# IR.net
KiCad netlist of a schematic drawn in Altium Designer
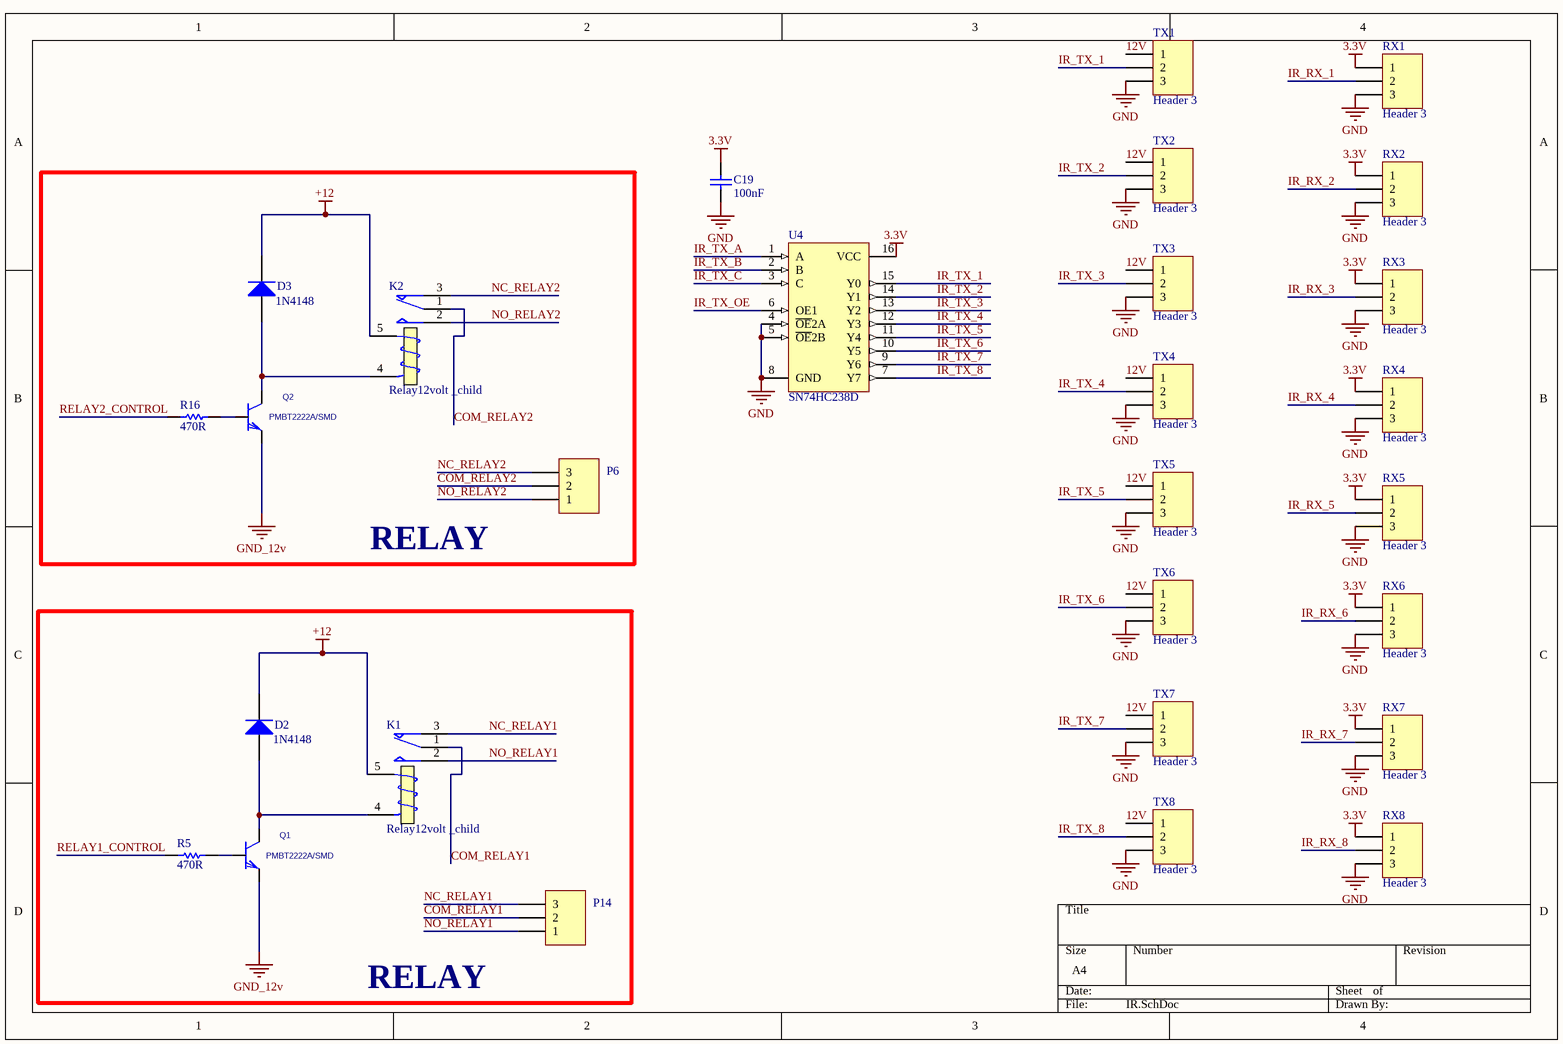
[diagram p0: IR.SchDoc]

(export (version "E")
  (design (tool "Eeschema 10.0.6"))
  (components
    (comp (ref "C19")
      (value "100nF")
      (footprint "0805")
      (description "Capacitor")
      (fields (field (name "PUBLISHER") "Altium Limited"))
      (libsource (lib "Miscellaneous Devices") (part "Cap"))
    )
    (comp (ref "D2")
      (value "1N4148")
      (footprint "diode smd")
      (description "1 Amp General Purpose Rectifier")
      (fields (field (name "PUBLISHER") "Altium Limited"))
      (libsource (lib "Miscellaneous Devices") (part "Diode 1N4007"))
    )
    (comp (ref "D3")
      (value "1N4148")
      (footprint "diode smd")
      (description "1 Amp General Purpose Rectifier")
      (fields (field (name "PUBLISHER") "Altium Limited"))
      (libsource (lib "Miscellaneous Devices") (part "Diode 1N4007"))
    )
    (comp (ref "K1")
      (value "Relay12volt _child")
      (footprint "relay")
      (description "SPDT Relay")
      (fields (field (name "PUBLISHER") "Altium Limited"))
      (libsource (lib "FLIB") (part "Relay"))
    )
    (comp (ref "K2")
      (value "Relay12volt _child")
      (footprint "relay")
      (description "SPDT Relay")
      (fields (field (name "PUBLISHER") "Altium Limited"))
      (libsource (lib "FLIB") (part "Relay"))
    )
    (comp (ref "P6")
      (value "kf301/3pin")
      (footprint "Blue Connector 1*3 -kf301")
      (fields (field (name "PUBLISHER") "Altium Limited"))
      (libsource (lib "") (part "Header 3_1"))
    )
    (comp (ref "P14")
      (value "kf301/3pin")
      (footprint "Blue Connector 1*3 -kf301")
      (fields (field (name "PUBLISHER") "Altium Limited"))
      (libsource (lib "") (part "Header 3_1"))
    )
    (comp (ref "Q1")
      (value "PMBT2222A/SMD")
      (footprint "transistoor1")
      (libsource (lib "*") (part "2N2222A/ZTX"))
    )
    (comp (ref "Q2")
      (value "PMBT2222A/SMD")
      (footprint "transistoor1")
      (libsource (lib "*") (part "2N2222A/ZTX"))
    )
    (comp (ref "R5")
      (value "470R")
      (footprint "res")
      (description "Resistor")
      (fields (field (name "PUBLISHER") "Altium Limited"))
      (libsource (lib "Miscellaneous Devices") (part "Res1"))
    )
    (comp (ref "R16")
      (value "470R")
      (footprint "res")
      (description "Resistor")
      (fields (field (name "PUBLISHER") "Altium Limited"))
      (libsource (lib "Miscellaneous Devices") (part "Res1"))
    )
    (comp (ref "RX1")
      (value "Header 3")
      (footprint "HDR1X3")
      (description "Header, 3-Pin")
      (fields (field (name "PUBLISHER") "Altium Limited"))
      (libsource (lib "Miscellaneous Connectors") (part "Header 3"))
    )
    (comp (ref "RX2")
      (value "Header 3")
      (footprint "HDR1X3")
      (description "Header, 3-Pin")
      (fields (field (name "PUBLISHER") "Altium Limited"))
      (libsource (lib "Miscellaneous Connectors") (part "Header 3"))
    )
    (comp (ref "RX3")
      (value "Header 3")
      (footprint "HDR1X3")
      (description "Header, 3-Pin")
      (fields (field (name "PUBLISHER") "Altium Limited"))
      (libsource (lib "Miscellaneous Connectors") (part "Header 3"))
    )
    (comp (ref "RX4")
      (value "Header 3")
      (footprint "HDR1X3")
      (description "Header, 3-Pin")
      (fields (field (name "PUBLISHER") "Altium Limited"))
      (libsource (lib "Miscellaneous Connectors") (part "Header 3"))
    )
    (comp (ref "RX5")
      (value "Header 3")
      (footprint "HDR1X3")
      (description "Header, 3-Pin")
      (fields (field (name "PUBLISHER") "Altium Limited"))
      (libsource (lib "Miscellaneous Connectors") (part "Header 3"))
    )
    (comp (ref "RX6")
      (value "Header 3")
      (footprint "HDR1X3")
      (description "Header, 3-Pin")
      (fields (field (name "PUBLISHER") "Altium Limited"))
      (libsource (lib "Miscellaneous Connectors") (part "Header 3"))
    )
    (comp (ref "RX7")
      (value "Header 3")
      (footprint "HDR1X3")
      (description "Header, 3-Pin")
      (fields (field (name "PUBLISHER") "Altium Limited"))
      (libsource (lib "Miscellaneous Connectors") (part "Header 3"))
    )
    (comp (ref "RX8")
      (value "Header 3")
      (footprint "HDR1X3")
      (description "Header, 3-Pin")
      (fields (field (name "PUBLISHER") "Altium Limited"))
      (libsource (lib "Miscellaneous Connectors") (part "Header 3"))
    )
    (comp (ref "TX1")
      (value "Header 3")
      (footprint "HDR1X3")
      (description "Header, 3-Pin")
      (fields (field (name "PUBLISHER") "Altium Limited"))
      (libsource (lib "Miscellaneous Connectors") (part "Header 3"))
    )
    (comp (ref "TX2")
      (value "Header 3")
      (footprint "HDR1X3")
      (description "Header, 3-Pin")
      (fields (field (name "PUBLISHER") "Altium Limited"))
      (libsource (lib "Miscellaneous Connectors") (part "Header 3"))
    )
    (comp (ref "TX3")
      (value "Header 3")
      (footprint "HDR1X3")
      (description "Header, 3-Pin")
      (fields (field (name "PUBLISHER") "Altium Limited"))
      (libsource (lib "Miscellaneous Connectors") (part "Header 3"))
    )
    (comp (ref "TX4")
      (value "Header 3")
      (footprint "HDR1X3")
      (description "Header, 3-Pin")
      (fields (field (name "PUBLISHER") "Altium Limited"))
      (libsource (lib "Miscellaneous Connectors") (part "Header 3"))
    )
    (comp (ref "TX5")
      (value "Header 3")
      (footprint "HDR1X3")
      (description "Header, 3-Pin")
      (fields (field (name "PUBLISHER") "Altium Limited"))
      (libsource (lib "Miscellaneous Connectors") (part "Header 3"))
    )
    (comp (ref "TX6")
      (value "Header 3")
      (footprint "HDR1X3")
      (description "Header, 3-Pin")
      (fields (field (name "PUBLISHER") "Altium Limited"))
      (libsource (lib "Miscellaneous Connectors") (part "Header 3"))
    )
    (comp (ref "TX7")
      (value "Header 3")
      (footprint "HDR1X3")
      (description "Header, 3-Pin")
      (fields (field (name "PUBLISHER") "Altium Limited"))
      (libsource (lib "Miscellaneous Connectors") (part "Header 3"))
    )
    (comp (ref "TX8")
      (value "Header 3")
      (footprint "HDR1X3")
      (description "Header, 3-Pin")
      (fields (field (name "PUBLISHER") "Altium Limited"))
      (libsource (lib "Miscellaneous Connectors") (part "Header 3"))
    )
    (comp (ref "U4")
      (value "SN74HC238D")
      (footprint "D016_N")
      (description "3-Line to 8-Line Decoder / Demultiplexer")
      (fields (field (name "PUBLISHER") "Altium Limited"))
      (libsource (lib "TI Logic Decoder Demux") (part "SN74HC238D"))
    )
  )
  (nets
    (net (code "1") (name "+12") (class "Default")
      (node (ref "D2") (pin "2") (pinfunction "K_2") (pintype "passive"))
      (node (ref "D3") (pin "2") (pinfunction "K_2") (pintype "passive"))
      (node (ref "K1") (pin "5") (pinfunction "5_5") (pintype "passive"))
      (node (ref "K2") (pin "5") (pinfunction "5_5") (pintype "passive"))
    )
    (net (code "2") (name "/12V") (class "Default")
      (node (ref "TX1") (pin "1") (pinfunction "1_1") (pintype "passive"))
      (node (ref "TX2") (pin "1") (pinfunction "1_1") (pintype "passive"))
      (node (ref "TX3") (pin "1") (pinfunction "1_1") (pintype "passive"))
      (node (ref "TX4") (pin "1") (pinfunction "1_1") (pintype "passive"))
      (node (ref "TX5") (pin "1") (pinfunction "1_1") (pintype "passive"))
      (node (ref "TX6") (pin "1") (pinfunction "1_1") (pintype "passive"))
      (node (ref "TX7") (pin "1") (pinfunction "1_1") (pintype "passive"))
      (node (ref "TX8") (pin "1") (pinfunction "1_1") (pintype "passive"))
    )
    (net (code "3") (name "/COM_RELAY1") (class "Default")
      (node (ref "K1") (pin "1") (pinfunction "COM_1") (pintype "passive"))
      (node (ref "P14") (pin "2") (pinfunction "2_2") (pintype "passive"))
    )
    (net (code "4") (name "/COM_RELAY2") (class "Default")
      (node (ref "K2") (pin "1") (pinfunction "COM_1") (pintype "passive"))
      (node (ref "P6") (pin "2") (pinfunction "2_2") (pintype "passive"))
    )
    (net (code "5") (name "/IR_RX_1") (class "Default")
      (node (ref "RX1") (pin "2") (pinfunction "2_2") (pintype "passive"))
    )
    (net (code "6") (name "/IR_RX_2") (class "Default")
      (node (ref "RX2") (pin "2") (pinfunction "2_2") (pintype "passive"))
    )
    (net (code "7") (name "/IR_RX_3") (class "Default")
      (node (ref "RX3") (pin "2") (pinfunction "2_2") (pintype "passive"))
    )
    (net (code "8") (name "/IR_RX_4") (class "Default")
      (node (ref "RX4") (pin "2") (pinfunction "2_2") (pintype "passive"))
    )
    (net (code "9") (name "/IR_RX_5") (class "Default")
      (node (ref "RX5") (pin "2") (pinfunction "2_2") (pintype "passive"))
    )
    (net (code "10") (name "/IR_RX_6") (class "Default")
      (node (ref "RX6") (pin "2") (pinfunction "2_2") (pintype "passive"))
    )
    (net (code "11") (name "/IR_RX_7") (class "Default")
      (node (ref "RX7") (pin "2") (pinfunction "2_2") (pintype "passive"))
    )
    (net (code "12") (name "/IR_RX_8") (class "Default")
      (node (ref "RX8") (pin "2") (pinfunction "2_2") (pintype "passive"))
    )
    (net (code "13") (name "/IR_TX_1") (class "Default")
      (node (ref "TX1") (pin "2") (pinfunction "2_2") (pintype "passive"))
      (node (ref "U4") (pin "15") (pinfunction "Y0_15") (pintype "output"))
    )
    (net (code "14") (name "/IR_TX_2") (class "Default")
      (node (ref "TX2") (pin "2") (pinfunction "2_2") (pintype "passive"))
      (node (ref "U4") (pin "14") (pinfunction "Y1_14") (pintype "output"))
    )
    (net (code "15") (name "/IR_TX_3") (class "Default")
      (node (ref "TX3") (pin "2") (pinfunction "2_2") (pintype "passive"))
      (node (ref "U4") (pin "13") (pinfunction "Y2_13") (pintype "output"))
    )
    (net (code "16") (name "/IR_TX_4") (class "Default")
      (node (ref "TX4") (pin "2") (pinfunction "2_2") (pintype "passive"))
      (node (ref "U4") (pin "12") (pinfunction "Y3_12") (pintype "output"))
    )
    (net (code "17") (name "/IR_TX_5") (class "Default")
      (node (ref "TX5") (pin "2") (pinfunction "2_2") (pintype "passive"))
      (node (ref "U4") (pin "11") (pinfunction "Y4_11") (pintype "output"))
    )
    (net (code "18") (name "/IR_TX_6") (class "Default")
      (node (ref "TX6") (pin "2") (pinfunction "2_2") (pintype "passive"))
      (node (ref "U4") (pin "10") (pinfunction "Y5_10") (pintype "output"))
    )
    (net (code "19") (name "/IR_TX_7") (class "Default")
      (node (ref "TX7") (pin "2") (pinfunction "2_2") (pintype "passive"))
      (node (ref "U4") (pin "9") (pinfunction "Y6_9") (pintype "output"))
    )
    (net (code "20") (name "/IR_TX_8") (class "Default")
      (node (ref "TX8") (pin "2") (pinfunction "2_2") (pintype "passive"))
      (node (ref "U4") (pin "7") (pinfunction "Y7_7") (pintype "output"))
    )
    (net (code "21") (name "/IR_TX_A") (class "Default")
      (node (ref "U4") (pin "1") (pinfunction "A_1") (pintype "input"))
    )
    (net (code "22") (name "/IR_TX_B") (class "Default")
      (node (ref "U4") (pin "2") (pinfunction "B_2") (pintype "input"))
    )
    (net (code "23") (name "/IR_TX_C") (class "Default")
      (node (ref "U4") (pin "3") (pinfunction "C_3") (pintype "input"))
    )
    (net (code "24") (name "/IR_TX_OE") (class "Default")
      (node (ref "U4") (pin "6") (pinfunction "OE1_6") (pintype "input"))
    )
    (net (code "25") (name "/NC_RELAY1") (class "Default")
      (node (ref "K1") (pin "3") (pinfunction "T1_3") (pintype "passive"))
      (node (ref "P14") (pin "3") (pinfunction "3_3") (pintype "passive"))
    )
    (net (code "26") (name "/NC_RELAY2") (class "Default")
      (node (ref "K2") (pin "3") (pinfunction "T1_3") (pintype "passive"))
      (node (ref "P6") (pin "3") (pinfunction "3_3") (pintype "passive"))
    )
    (net (code "27") (name "/NO_RELAY1") (class "Default")
      (node (ref "K1") (pin "2") (pinfunction "NO_2") (pintype "passive"))
      (node (ref "P14") (pin "1") (pinfunction "1_1") (pintype "passive"))
    )
    (net (code "28") (name "/NO_RELAY2") (class "Default")
      (node (ref "K2") (pin "2") (pinfunction "NO_2") (pintype "passive"))
      (node (ref "P6") (pin "1") (pinfunction "1_1") (pintype "passive"))
    )
    (net (code "29") (name "/RELAY1_CONTROL") (class "Default")
      (node (ref "R5") (pin "1") (pinfunction "1_1") (pintype "passive"))
    )
    (net (code "30") (name "/RELAY2_CONTROL") (class "Default")
      (node (ref "R16") (pin "1") (pinfunction "1_1") (pintype "passive"))
    )
    (net (code "31") (name "3.3V") (class "Default")
      (node (ref "C19") (pin "1") (pinfunction "1_1") (pintype "passive"))
      (node (ref "RX1") (pin "1") (pinfunction "1_1") (pintype "passive"))
      (node (ref "RX2") (pin "1") (pinfunction "1_1") (pintype "passive"))
      (node (ref "RX3") (pin "1") (pinfunction "1_1") (pintype "passive"))
      (node (ref "RX4") (pin "1") (pinfunction "1_1") (pintype "passive"))
      (node (ref "RX5") (pin "1") (pinfunction "1_1") (pintype "passive"))
      (node (ref "RX6") (pin "1") (pinfunction "1_1") (pintype "passive"))
      (node (ref "RX7") (pin "1") (pinfunction "1_1") (pintype "passive"))
      (node (ref "RX8") (pin "1") (pinfunction "1_1") (pintype "passive"))
      (node (ref "U4") (pin "16") (pinfunction "VCC_16") (pintype "power_in"))
    )
    (net (code "32") (name "GND") (class "Default")
      (node (ref "C19") (pin "2") (pinfunction "2_2") (pintype "passive"))
      (node (ref "RX1") (pin "3") (pinfunction "3_3") (pintype "passive"))
      (node (ref "RX2") (pin "3") (pinfunction "3_3") (pintype "passive"))
      (node (ref "RX3") (pin "3") (pinfunction "3_3") (pintype "passive"))
      (node (ref "RX4") (pin "3") (pinfunction "3_3") (pintype "passive"))
      (node (ref "RX5") (pin "3") (pinfunction "3_3") (pintype "passive"))
      (node (ref "RX6") (pin "3") (pinfunction "3_3") (pintype "passive"))
      (node (ref "RX7") (pin "3") (pinfunction "3_3") (pintype "passive"))
      (node (ref "RX8") (pin "3") (pinfunction "3_3") (pintype "passive"))
      (node (ref "TX1") (pin "3") (pinfunction "3_3") (pintype "passive"))
      (node (ref "TX2") (pin "3") (pinfunction "3_3") (pintype "passive"))
      (node (ref "TX3") (pin "3") (pinfunction "3_3") (pintype "passive"))
      (node (ref "TX4") (pin "3") (pinfunction "3_3") (pintype "passive"))
      (node (ref "TX5") (pin "3") (pinfunction "3_3") (pintype "passive"))
      (node (ref "TX6") (pin "3") (pinfunction "3_3") (pintype "passive"))
      (node (ref "TX7") (pin "3") (pinfunction "3_3") (pintype "passive"))
      (node (ref "TX8") (pin "3") (pinfunction "3_3") (pintype "passive"))
      (node (ref "U4") (pin "4") (pinfunction "~{OE}2A_4") (pintype "input"))
      (node (ref "U4") (pin "5") (pinfunction "~{OE}2B_5") (pintype "input"))
      (node (ref "U4") (pin "8") (pinfunction "GND_8") (pintype "power_in"))
    )
    (net (code "33") (name "GND_12v") (class "Default")
      (node (ref "Q1") (pin "3") (pinfunction "E_3") (pintype "passive"))
      (node (ref "Q2") (pin "3") (pinfunction "E_3") (pintype "passive"))
    )
    (net (code "34") (name "Net-(D2-A)") (class "Default")
      (node (ref "D2") (pin "1") (pinfunction "A_1") (pintype "passive"))
      (node (ref "K1") (pin "4") (pinfunction "T2_4") (pintype "passive"))
      (node (ref "Q1") (pin "2") (pinfunction "C_2") (pintype "passive"))
    )
    (net (code "35") (name "Net-(D3-A)") (class "Default")
      (node (ref "D3") (pin "1") (pinfunction "A_1") (pintype "passive"))
      (node (ref "K2") (pin "4") (pinfunction "T2_4") (pintype "passive"))
      (node (ref "Q2") (pin "2") (pinfunction "C_2") (pintype "passive"))
    )
    (net (code "36") (name "Net-(Q1-B)") (class "Default")
      (node (ref "Q1") (pin "1") (pinfunction "B_1") (pintype "passive"))
      (node (ref "R5") (pin "2") (pinfunction "2_2") (pintype "passive"))
    )
    (net (code "37") (name "Net-(Q2-B)") (class "Default")
      (node (ref "Q2") (pin "1") (pinfunction "B_1") (pintype "passive"))
      (node (ref "R16") (pin "2") (pinfunction "2_2") (pintype "passive"))
    )
  )
)
